# ext.net
KiCad netlist of a schematic drawn in Altium Designer
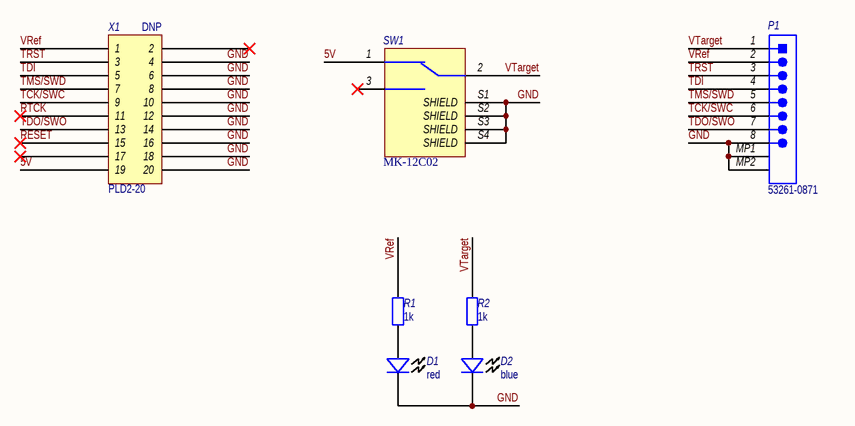
[diagram p0: ext.SchDoc]

(export (version "E")
  (design (tool "Eeschema 10.0.6"))
  (components
    (comp (ref "D1")
      (value "red")
      (footprint "LED_0603")
      (fields (field (name "Comment") "LED"))
      (libsource (lib "Diod") (part "LED"))
    )
    (comp (ref "D2")
      (value "blue")
      (footprint "LED_0603")
      (fields (field (name "Comment") "LED"))
      (libsource (lib "Diod") (part "LED"))
    )
    (comp (ref "P1")
      (value "PicoBlade_53261-0871")
      (footprint "53261-0871")
      (description "Male Header, Pitch 1.25 mm, 1 x 8 Position, Height 3.4 mm, -40 to 85 degC, RoHS, Tape and Reel")
      (fields (field (name "НАИМЕНОВАНИЕ") "53261-0871"))
      (libsource (lib "Connector") (part "PicoBlade_53261-0871"))
    )
    (comp (ref "R1")
      (value "1k")
      (footprint "SMD_0603")
      (description "Resistor")
      (fields (field (name "Comment") "OSM R1-8"))
      (libsource (lib "Passive") (part "Resistor"))
    )
    (comp (ref "R2")
      (value "1k")
      (footprint "SMD_0603")
      (description "Resistor")
      (fields (field (name "Comment") "OSM R1-8"))
      (libsource (lib "Passive") (part "Resistor"))
    )
    (comp (ref "SW1")
      (value "MK-12C02")
      (footprint "PCBComponent_1")
      (description "Surface Mount, Right Angle 1A SPDT 6V Black 10,000 Cycles SMD,6.6x1.4mm Slide Switches")
      (libsource (lib "Switch") (part "MK-12C02"))
    )
    (comp (ref "X1")
      (value "Header 2X20")
      (footprint "DS1013-20R")
      (description "Header, 20-Pin, Dual row")
      (fields (field (name "НАИМЕНОВАНИЕ") "PLD2-20") (field (name "DNP") "DNP"))
      (libsource (lib "Connector") (part "Header 2X20"))
    )
  )
  (nets
    (net (code "1") (name "/5V") (class "Default")
      (node (ref "SW1") (pin "1") (pinfunction "1_1") (pintype "passive"))
      (node (ref "X1") (pin "19") (pinfunction "19_19") (pintype "passive"))
    )
    (net (code "2") (name "/GND") (class "Default")
      (node (ref "D1") (pin "2") (pinfunction "K_2") (pintype "passive"))
      (node (ref "D2") (pin "2") (pinfunction "K_2") (pintype "passive"))
      (node (ref "P1") (pin "8") (pinfunction "8_8") (pintype "passive"))
      (node (ref "P1") (pin "MP1") (pinfunction "MP1_MP1") (pintype "passive"))
      (node (ref "P1") (pin "MP2") (pinfunction "MP2_MP2") (pintype "passive"))
      (node (ref "SW1") (pin "S1") (pinfunction "SHIELD_S1") (pintype "passive"))
      (node (ref "SW1") (pin "S2") (pinfunction "SHIELD_S2") (pintype "passive"))
      (node (ref "SW1") (pin "S3") (pinfunction "SHIELD_S3") (pintype "passive"))
      (node (ref "SW1") (pin "S4") (pinfunction "SHIELD_S4") (pintype "passive"))
      (node (ref "X1") (pin "10") (pinfunction "10_10") (pintype "passive"))
      (node (ref "X1") (pin "12") (pinfunction "12_12") (pintype "passive"))
      (node (ref "X1") (pin "14") (pinfunction "14_14") (pintype "passive"))
      (node (ref "X1") (pin "16") (pinfunction "16_16") (pintype "passive"))
      (node (ref "X1") (pin "18") (pinfunction "18_18") (pintype "passive"))
      (node (ref "X1") (pin "20") (pinfunction "20_20") (pintype "passive"))
      (node (ref "X1") (pin "4") (pinfunction "4_4") (pintype "passive"))
      (node (ref "X1") (pin "6") (pinfunction "6_6") (pintype "passive"))
      (node (ref "X1") (pin "8") (pinfunction "8_8") (pintype "passive"))
    )
    (net (code "3") (name "/RESET") (class "Default")
      (node (ref "X1") (pin "15") (pinfunction "15_15") (pintype "passive+no_connect"))
    )
    (net (code "4") (name "/RTCK") (class "Default")
      (node (ref "X1") (pin "11") (pinfunction "11_11") (pintype "passive+no_connect"))
    )
    (net (code "5") (name "/TCK{slash}SWC") (class "Default")
      (node (ref "P1") (pin "6") (pinfunction "6_6") (pintype "passive"))
      (node (ref "X1") (pin "9") (pinfunction "9_9") (pintype "passive"))
    )
    (net (code "6") (name "/TDI") (class "Default")
      (node (ref "P1") (pin "4") (pinfunction "4_4") (pintype "passive"))
      (node (ref "X1") (pin "5") (pinfunction "5_5") (pintype "passive"))
    )
    (net (code "7") (name "/TDO{slash}SWO") (class "Default")
      (node (ref "P1") (pin "7") (pinfunction "7_7") (pintype "passive"))
      (node (ref "X1") (pin "13") (pinfunction "13_13") (pintype "passive"))
    )
    (net (code "8") (name "/TMS{slash}SWD") (class "Default")
      (node (ref "P1") (pin "5") (pinfunction "5_5") (pintype "passive"))
      (node (ref "X1") (pin "7") (pinfunction "7_7") (pintype "passive"))
    )
    (net (code "9") (name "/TRST") (class "Default")
      (node (ref "P1") (pin "3") (pinfunction "3_3") (pintype "passive"))
      (node (ref "X1") (pin "3") (pinfunction "3_3") (pintype "passive"))
    )
    (net (code "10") (name "/VRef") (class "Default")
      (node (ref "P1") (pin "2") (pinfunction "2_2") (pintype "passive"))
      (node (ref "R1") (pin "2") (pinfunction "2_2") (pintype "passive"))
      (node (ref "X1") (pin "1") (pinfunction "1_1") (pintype "passive"))
    )
    (net (code "11") (name "/VTarget") (class "Default")
      (node (ref "P1") (pin "1") (pinfunction "1_1") (pintype "passive"))
      (node (ref "R2") (pin "2") (pinfunction "2_2") (pintype "passive"))
      (node (ref "SW1") (pin "2") (pinfunction "2_2") (pintype "passive"))
    )
    (net (code "12") (name "Net-(D1-A)") (class "Default")
      (node (ref "D1") (pin "1") (pinfunction "A_1") (pintype "passive"))
      (node (ref "R1") (pin "1") (pinfunction "1_1") (pintype "passive"))
    )
    (net (code "13") (name "Net-(D2-A)") (class "Default")
      (node (ref "D2") (pin "1") (pinfunction "A_1") (pintype "passive"))
      (node (ref "R2") (pin "1") (pinfunction "1_1") (pintype "passive"))
    )
    (net (code "14") (name "unconnected-(SW1-Pad3)") (class "Default")
      (node (ref "SW1") (pin "3") (pinfunction "3_3") (pintype "passive+no_connect"))
    )
    (net (code "15") (name "unconnected-(X1-Pad2)") (class "Default")
      (node (ref "X1") (pin "2") (pinfunction "2_2") (pintype "passive+no_connect"))
    )
    (net (code "16") (name "unconnected-(X1-Pad17)") (class "Default")
      (node (ref "X1") (pin "17") (pinfunction "17_17") (pintype "passive+no_connect"))
    )
  )
)
